# Probe-Scope_Controller_v1_0.net
KiCad netlist of a schematic drawn in Altium Designer
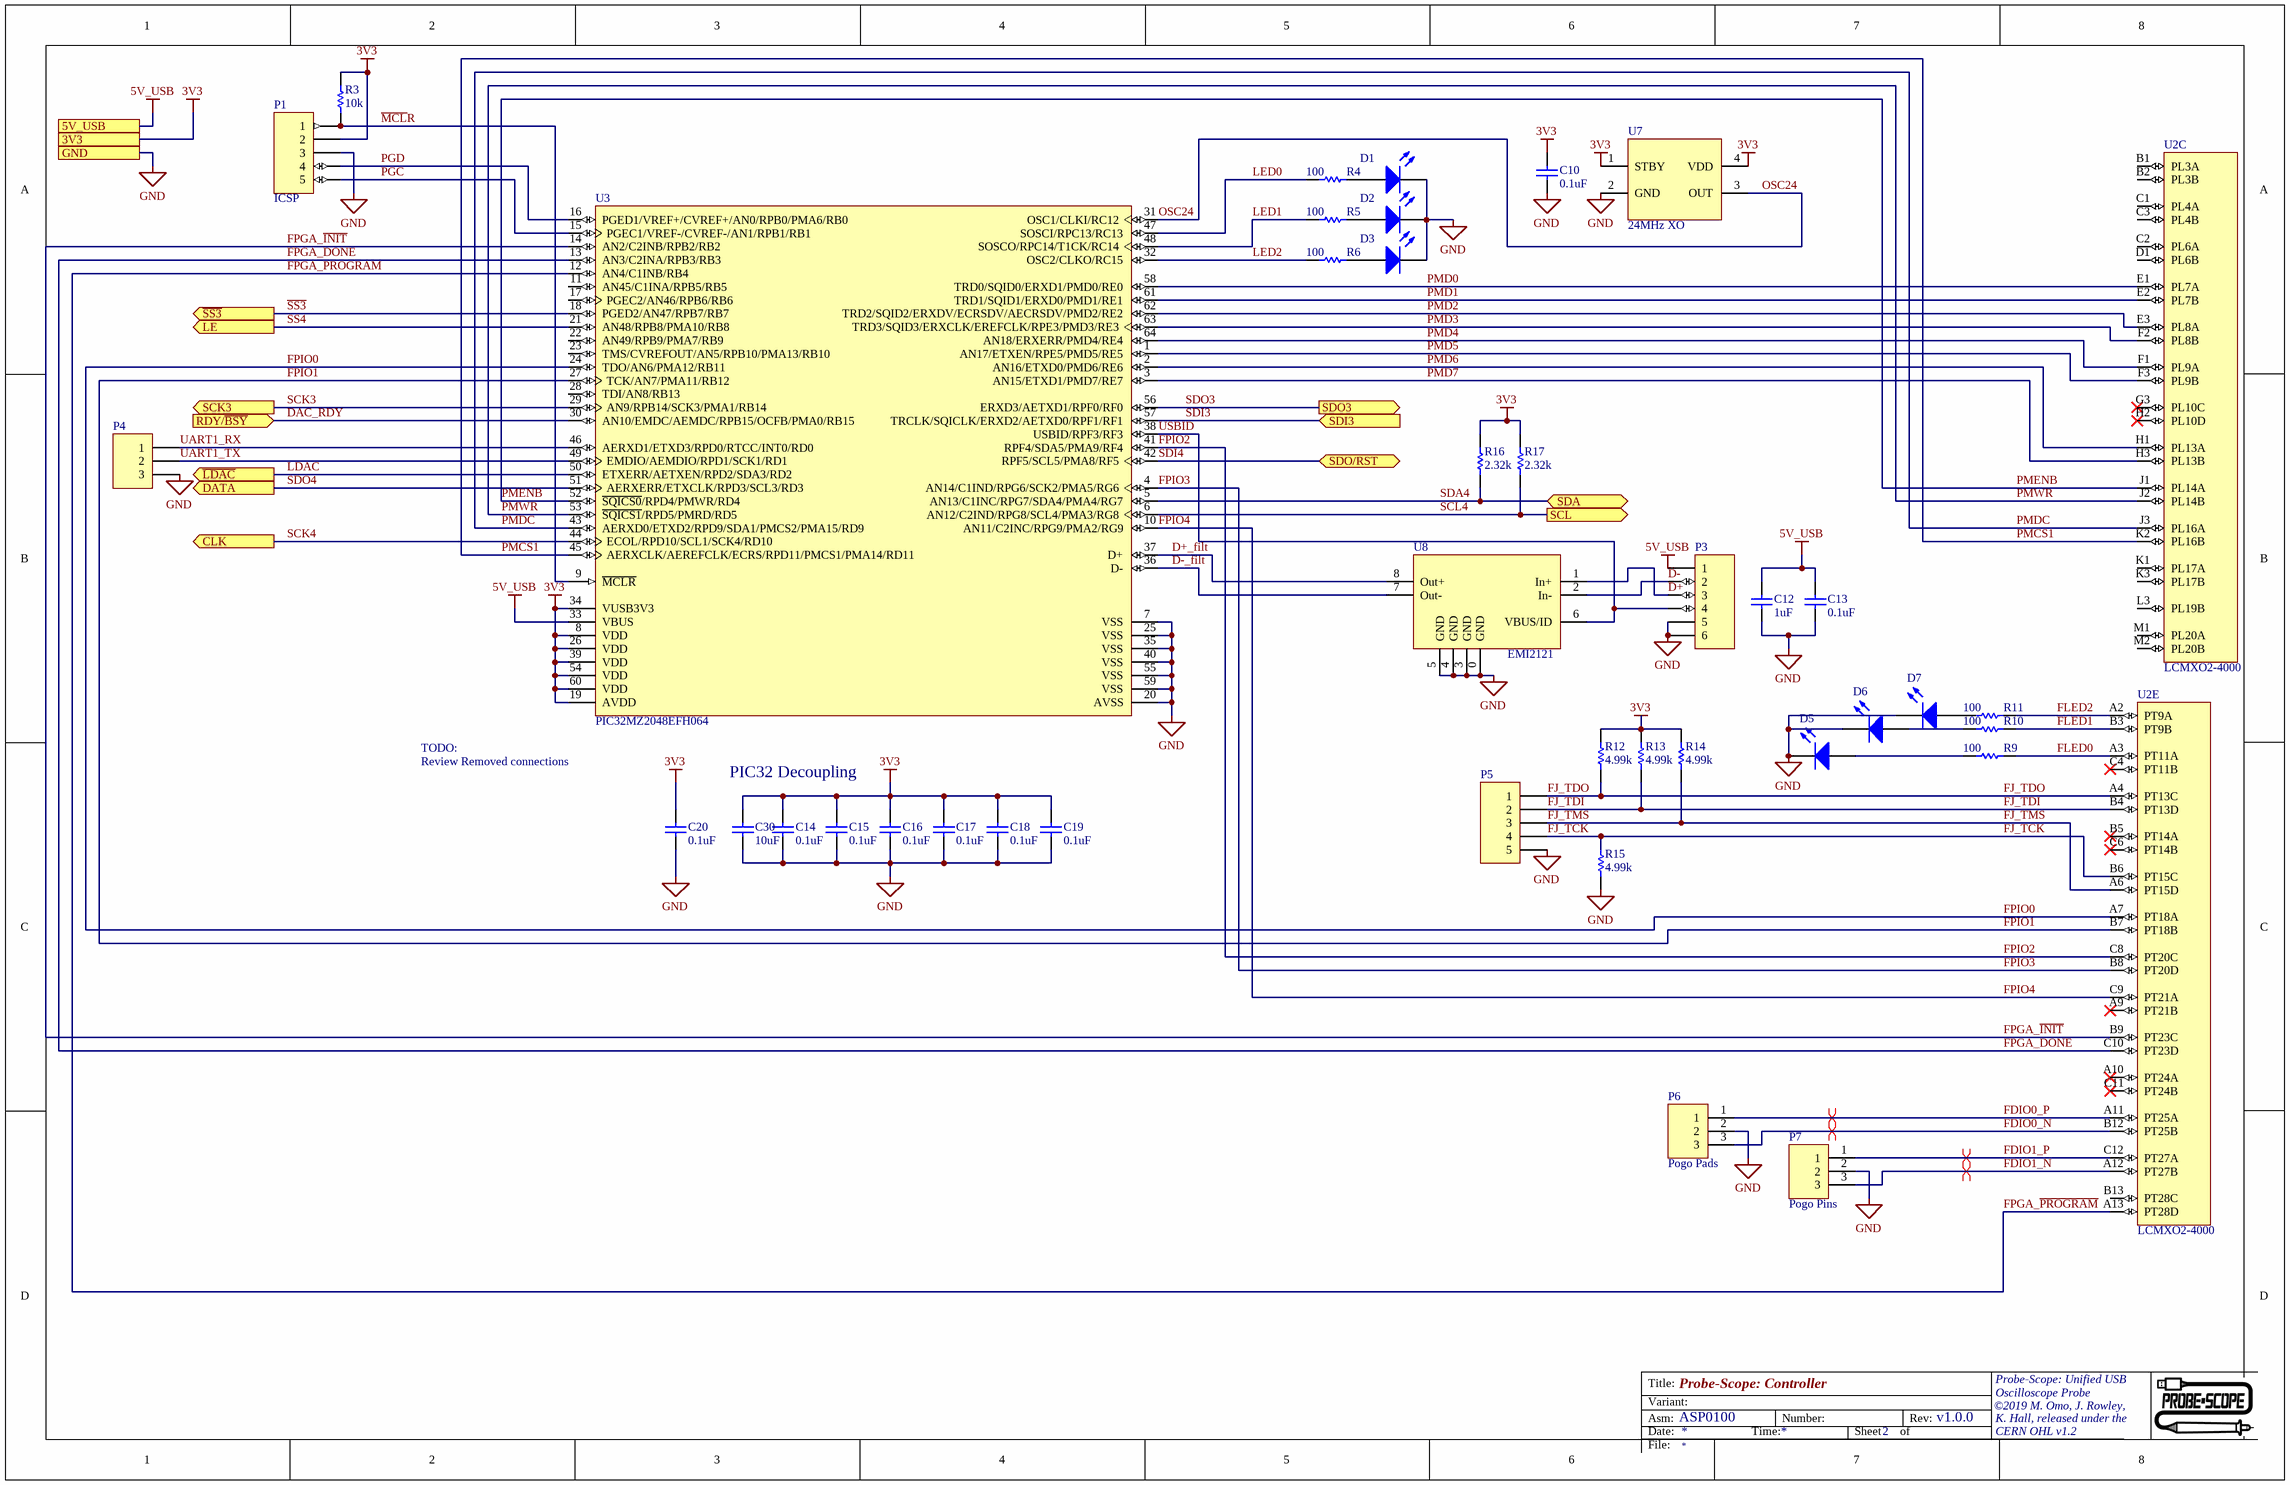
[diagram p0: Probe-Scope Controller v1.0.SchDoc]

(export (version "E")
  (design (tool "Eeschema 10.0.6"))
  (components
    (comp (ref "C10")
      (value "0.1uF")
      (footprint "0402(1005)")
      (fields
        (field (name "MANF") "Samsung Electro-Mechanics")
        (field (name "TOLERANCE") "10")
        (field (name "VOLTAGE") "6.3")
        (field (name "MODIFIED BY") "jrowley")
        (field (name "APPROVED") "False")
      )
      (libsource (lib "MENG Database Library VPN") (part "Cap"))
    )
    (comp (ref "C12")
      (value "1uF")
      (footprint "0402(1005)")
      (fields
        (field (name "MANF") "Murata Electronics")
        (field (name "TOLERANCE") "10")
        (field (name "Comment") "10V")
        (field (name "MODIFIED BY") "jrowley")
        (field (name "APPROVED") "False")
      )
      (libsource (lib "MENG Database Library VPN") (part "Cap"))
    )
    (comp (ref "C13")
      (value "0.1uF")
      (footprint "0402(1005)")
      (fields
        (field (name "MANF") "Samsung Electro-Mechanics")
        (field (name "TOLERANCE") "10")
        (field (name "VOLTAGE") "6.3")
        (field (name "MODIFIED BY") "jrowley")
        (field (name "APPROVED") "False")
      )
      (libsource (lib "MENG Database Library VPN") (part "Cap"))
    )
    (comp (ref "C14")
      (value "0.1uF")
      (footprint "0402(1005)")
      (fields
        (field (name "MANF") "Samsung Electro-Mechanics")
        (field (name "TOLERANCE") "10")
        (field (name "VOLTAGE") "6.3")
        (field (name "MODIFIED BY") "jrowley")
        (field (name "APPROVED") "False")
      )
      (libsource (lib "MENG Database Library VPN") (part "Cap"))
    )
    (comp (ref "C15")
      (value "0.1uF")
      (footprint "0402(1005)")
      (fields
        (field (name "MANF") "Samsung Electro-Mechanics")
        (field (name "TOLERANCE") "10")
        (field (name "VOLTAGE") "6.3")
        (field (name "MODIFIED BY") "jrowley")
        (field (name "APPROVED") "False")
      )
      (libsource (lib "MENG Database Library VPN") (part "Cap"))
    )
    (comp (ref "C16")
      (value "0.1uF")
      (footprint "0402(1005)")
      (fields
        (field (name "MANF") "Samsung Electro-Mechanics")
        (field (name "TOLERANCE") "10")
        (field (name "VOLTAGE") "6.3")
        (field (name "MODIFIED BY") "jrowley")
        (field (name "APPROVED") "False")
      )
      (libsource (lib "MENG Database Library VPN") (part "Cap"))
    )
    (comp (ref "C17")
      (value "0.1uF")
      (footprint "0402(1005)")
      (fields
        (field (name "MANF") "Samsung Electro-Mechanics")
        (field (name "TOLERANCE") "10")
        (field (name "VOLTAGE") "6.3")
        (field (name "MODIFIED BY") "jrowley")
        (field (name "APPROVED") "False")
      )
      (libsource (lib "MENG Database Library VPN") (part "Cap"))
    )
    (comp (ref "C18")
      (value "0.1uF")
      (footprint "0402(1005)")
      (fields
        (field (name "MANF") "Samsung Electro-Mechanics")
        (field (name "TOLERANCE") "10")
        (field (name "VOLTAGE") "6.3")
        (field (name "MODIFIED BY") "jrowley")
        (field (name "APPROVED") "False")
      )
      (libsource (lib "MENG Database Library VPN") (part "Cap"))
    )
    (comp (ref "C19")
      (value "0.1uF")
      (footprint "0402(1005)")
      (fields
        (field (name "MANF") "Samsung Electro-Mechanics")
        (field (name "TOLERANCE") "10")
        (field (name "VOLTAGE") "6.3")
        (field (name "MODIFIED BY") "jrowley")
        (field (name "APPROVED") "False")
      )
      (libsource (lib "MENG Database Library VPN") (part "Cap"))
    )
    (comp (ref "C20")
      (value "0.1uF")
      (footprint "0402(1005)")
      (fields
        (field (name "MANF") "Samsung Electro-Mechanics")
        (field (name "TOLERANCE") "10")
        (field (name "VOLTAGE") "6.3")
        (field (name "MODIFIED BY") "jrowley")
        (field (name "APPROVED") "False")
      )
      (libsource (lib "MENG Database Library VPN") (part "Cap"))
    )
    (comp (ref "C30")
      (value "10uF")
      (footprint "0603(1608)")
      (fields
        (field (name "MANF") "Samsung Electro-Mechanics")
        (field (name "TOLERANCE") "20")
        (field (name "VOLTAGE") "25")
        (field (name "MODIFIED BY") "sotterbacher")
        (field (name "APPROVED") "True")
      )
      (libsource (lib "MENG Database Library VPN") (part "Cap"))
    )
    (comp (ref "D1")
      (value "Green")
      (footprint "0603(1608) LED")
      (fields
        (field (name "MANF") "OSRAM")
        (field (name "VOLTAGE") "1.7")
        (field (name "MODIFIED BY") "pmarcus")
        (field (name "APPROVED") "True")
      )
      (libsource (lib "MENG Database Library VPN") (part "LED0"))
    )
    (comp (ref "D2")
      (value "Green")
      (footprint "0603(1608) LED")
      (fields
        (field (name "MANF") "OSRAM")
        (field (name "VOLTAGE") "1.7")
        (field (name "MODIFIED BY") "pmarcus")
        (field (name "APPROVED") "True")
      )
      (libsource (lib "MENG Database Library VPN") (part "LED0"))
    )
    (comp (ref "D3")
      (value "Green")
      (footprint "0603(1608) LED")
      (fields
        (field (name "MANF") "OSRAM")
        (field (name "VOLTAGE") "1.7")
        (field (name "MODIFIED BY") "pmarcus")
        (field (name "APPROVED") "True")
      )
      (libsource (lib "MENG Database Library VPN") (part "LED0"))
    )
    (comp (ref "D5")
      (value "Green")
      (footprint "0603(1608) LED")
      (fields
        (field (name "MANF") "OSRAM")
        (field (name "VOLTAGE") "1.7")
        (field (name "MODIFIED BY") "pmarcus")
        (field (name "APPROVED") "True")
      )
      (libsource (lib "MENG Database Library VPN") (part "LED0"))
    )
    (comp (ref "D6")
      (value "Green")
      (footprint "0603(1608) LED")
      (fields
        (field (name "MANF") "OSRAM")
        (field (name "VOLTAGE") "1.7")
        (field (name "MODIFIED BY") "pmarcus")
        (field (name "APPROVED") "True")
      )
      (libsource (lib "MENG Database Library VPN") (part "LED0"))
    )
    (comp (ref "D7")
      (value "Green")
      (footprint "0603(1608) LED")
      (fields
        (field (name "MANF") "OSRAM")
        (field (name "VOLTAGE") "1.7")
        (field (name "MODIFIED BY") "pmarcus")
        (field (name "APPROVED") "True")
      )
      (libsource (lib "MENG Database Library VPN") (part "LED0"))
    )
    (comp (ref "P1")
      (value "ICSP")
      (footprint "MOLEX PICOBLADE 5 POS")
      (fields
        (field (name "MANF") "Molex")
        (field (name "VOLTAGE") "125")
        (field (name "MODIFIED BY") "pmarcus")
        (field (name "APPROVED") "True")
      )
      (libsource (lib "MENG Database Library VPN") (part "Header 5"))
    )
    (comp (ref "P3")
      (value "Micro USB")
      (footprint "USB Micro B ZX62")
      (fields
        (field (name "MANF") "Amphenol FCI")
        (field (name "VOLTAGE") "100")
        (field (name "MODIFIED BY") "jrowley")
        (field (name "APPROVED") "False")
      )
      (libsource (lib "MENG Database Library VPN") (part "Header 6"))
    )
    (comp (ref "P4")
      (value "PicoBlade 3")
      (footprint "MOLEX PICOBLADE 3 POS")
      (fields
        (field (name "MANF") "Molex")
        (field (name "VOLTAGE") "125")
        (field (name "MODIFIED BY") "rlaity")
        (field (name "APPROVED") "True")
      )
      (libsource (lib "MENG Database Library 18") (part "Header 3"))
    )
    (comp (ref "P5")
      (value "PicoBlade 5")
      (footprint "MOLEX PICOBLADE 5 POS")
      (fields
        (field (name "MANF") "Molex")
        (field (name "VOLTAGE") "125")
        (field (name "MODIFIED BY") "pmarcus")
        (field (name "APPROVED") "True")
      )
      (libsource (lib "MENG Database Library 18") (part "Header 5"))
    )
    (comp (ref "P6")
      (value "Pogo Pads")
      (footprint "POGO_PADS_3")
      (libsource (lib "PS v1.0") (part "POGO_PADS_3"))
    )
    (comp (ref "P7")
      (value "Pogo Pins")
      (footprint "POGO_PINS_3")
      (fields (field (name "MANF") "Prec-Dip"))
      (libsource (lib "PS v1.0") (part "POGO_PINS_3"))
    )
    (comp (ref "R3")
      (value "10k")
      (footprint "0402(1005)")
      (fields
        (field (name "MANF") "Stackpole Electronics")
        (field (name "TOLERANCE") "1")
        (field (name "POWER") "0.0625")
        (field (name "MODIFIED BY") "jrowley")
        (field (name "APPROVED") "False")
      )
      (libsource (lib "MENG Database Library VPN") (part "Res1"))
    )
    (comp (ref "R4")
      (value "100")
      (footprint "0402(1005)")
      (fields
        (field (name "MANF") "Yageo")
        (field (name "TOLERANCE") "1")
        (field (name "POWER") "0.0625")
        (field (name "MODIFIED BY") "jrowley")
        (field (name "APPROVED") "False")
      )
      (libsource (lib "MENG Database Library VPN") (part "Res1"))
    )
    (comp (ref "R5")
      (value "100")
      (footprint "0402(1005)")
      (fields
        (field (name "MANF") "Yageo")
        (field (name "TOLERANCE") "1")
        (field (name "POWER") "0.0625")
        (field (name "MODIFIED BY") "jrowley")
        (field (name "APPROVED") "False")
      )
      (libsource (lib "MENG Database Library VPN") (part "Res1"))
    )
    (comp (ref "R6")
      (value "100")
      (footprint "0402(1005)")
      (fields
        (field (name "MANF") "Yageo")
        (field (name "TOLERANCE") "1")
        (field (name "POWER") "0.0625")
        (field (name "MODIFIED BY") "jrowley")
        (field (name "APPROVED") "False")
      )
      (libsource (lib "MENG Database Library VPN") (part "Res1"))
    )
    (comp (ref "R9")
      (value "100")
      (footprint "0402(1005)")
      (fields
        (field (name "MANF") "Yageo")
        (field (name "TOLERANCE") "1")
        (field (name "POWER") "0.0625")
        (field (name "MODIFIED BY") "jrowley")
        (field (name "APPROVED") "False")
      )
      (libsource (lib "MENG Database Library VPN") (part "Res1"))
    )
    (comp (ref "R10")
      (value "100")
      (footprint "0402(1005)")
      (fields
        (field (name "MANF") "Yageo")
        (field (name "TOLERANCE") "1")
        (field (name "POWER") "0.0625")
        (field (name "MODIFIED BY") "jrowley")
        (field (name "APPROVED") "False")
      )
      (libsource (lib "MENG Database Library VPN") (part "Res1"))
    )
    (comp (ref "R11")
      (value "100")
      (footprint "0402(1005)")
      (fields
        (field (name "MANF") "Yageo")
        (field (name "TOLERANCE") "1")
        (field (name "POWER") "0.0625")
        (field (name "MODIFIED BY") "jrowley")
        (field (name "APPROVED") "False")
      )
      (libsource (lib "MENG Database Library VPN") (part "Res1"))
    )
    (comp (ref "R12")
      (value "4.99k")
      (footprint "0402(1005)")
      (fields
        (field (name "MANF") "Yageo")
        (field (name "TOLERANCE") "1")
        (field (name "POWER") "0.063")
        (field (name "MODIFIED BY") "khall")
        (field (name "APPROVED") "False")
      )
      (libsource (lib "MENG Database Library VPN") (part "Res1"))
    )
    (comp (ref "R13")
      (value "4.99k")
      (footprint "0402(1005)")
      (fields
        (field (name "MANF") "Yageo")
        (field (name "TOLERANCE") "1")
        (field (name "POWER") "0.063")
        (field (name "MODIFIED BY") "khall")
        (field (name "APPROVED") "False")
      )
      (libsource (lib "MENG Database Library VPN") (part "Res1"))
    )
    (comp (ref "R14")
      (value "4.99k")
      (footprint "0402(1005)")
      (fields
        (field (name "MANF") "Yageo")
        (field (name "TOLERANCE") "1")
        (field (name "POWER") "0.063")
        (field (name "MODIFIED BY") "khall")
        (field (name "APPROVED") "False")
      )
      (libsource (lib "MENG Database Library VPN") (part "Res1"))
    )
    (comp (ref "R15")
      (value "4.99k")
      (footprint "0402(1005)")
      (fields
        (field (name "MANF") "Yageo")
        (field (name "TOLERANCE") "1")
        (field (name "POWER") "0.063")
        (field (name "MODIFIED BY") "khall")
        (field (name "APPROVED") "False")
      )
      (libsource (lib "MENG Database Library VPN") (part "Res1"))
    )
    (comp (ref "R16")
      (value "2.32k")
      (footprint "0402(1005)")
      (fields
        (field (name "MANF") "Stackpole Electronics")
        (field (name "TOLERANCE") "1")
        (field (name "POWER") "0.0625")
        (field (name "MODIFIED BY") "khall")
        (field (name "APPROVED") "False")
      )
      (libsource (lib "MENG Database Library VPN") (part "Res1"))
    )
    (comp (ref "R17")
      (value "2.32k")
      (footprint "0402(1005)")
      (fields
        (field (name "MANF") "Stackpole Electronics")
        (field (name "TOLERANCE") "1")
        (field (name "POWER") "0.0625")
        (field (name "MODIFIED BY") "khall")
        (field (name "APPROVED") "False")
      )
      (libsource (lib "MENG Database Library VPN") (part "Res1"))
    )
    (comp (ref "U2")
      (value "LCMXO2-4000")
      (footprint "132_Ball_csBGA_MachXO2")
      (fields (field (name "MANF") "Lattice Semiconductor"))
      (libsource (lib "PS v1.0") (part "MachXO2-4000"))
    )
    (comp (ref "U3")
      (value "PIC32MZ2048EFH064")
      (footprint "TSQFP50P1200X1200X120-64L")
      (description "Microchip PIC32MZ EF Series 64-pin")
      (fields (field (name "MANF") "Microchip Technology"))
      (libsource (lib "PS v1.0") (part "PIC32MZ2048EFH064-I/PT"))
    )
    (comp (ref "U7")
      (value "24MHz XO")
      (footprint "DSC60xxC")
      (fields
        (field (name "MANF") "Microchip")
        (field (name "MODIFIED BY") "jrowley")
        (field (name "APPROVED") "False")
      )
      (libsource (lib "MENG Database Library VPN") (part "DSC60x1"))
    )
    (comp (ref "U8")
      (value "EMI2121")
      (footprint "EMI2121")
      (fields
        (field (name "MANF") "On Semiconductor")
        (field (name "MODIFIED BY") "jrowley")
        (field (name "APPROVED") "False")
      )
      (libsource (lib "MENG Database Library VPN") (part "EMI2121"))
    )
  )
  (nets
    (net (code "1") (name "/D+") (class "Default")
      (node (ref "P3") (pin "3") (pinfunction "3_3") (pintype "bidirectional"))
      (node (ref "U8") (pin "1") (pinfunction "In+_1") (pintype "passive"))
    )
    (net (code "2") (name "/D+_filt") (class "Default")
      (node (ref "U3") (pin "37") (pinfunction "D+_37") (pintype "bidirectional"))
      (node (ref "U8") (pin "8") (pinfunction "Out+_8") (pintype "passive"))
    )
    (net (code "3") (name "/D-") (class "Default")
      (node (ref "P3") (pin "2") (pinfunction "2_2") (pintype "bidirectional"))
      (node (ref "U8") (pin "2") (pinfunction "In-_2") (pintype "passive"))
    )
    (net (code "4") (name "/D-_filt") (class "Default")
      (node (ref "U3") (pin "36") (pinfunction "D-_36") (pintype "bidirectional"))
      (node (ref "U8") (pin "7") (pinfunction "Out-_7") (pintype "passive"))
    )
    (net (code "5") (name "/DAC_RDY") (class "Default")
      (node (ref "U3") (pin "30") (pinfunction "AN10/EMDC/AEMDC/RPB15/OCFB/PMA0/RB15_30") (pintype "bidirectional"))
    )
    (net (code "6") (name "/FDIO0_N") (class "Default")
      (node (ref "P6") (pin "3") (pinfunction "3_3") (pintype "passive"))
      (node (ref "U2") (pin "B12") (pinfunction "PT25B_B12") (pintype "bidirectional"))
    )
    (net (code "7") (name "/FDIO0_P") (class "Default")
      (node (ref "P6") (pin "1") (pinfunction "1_1") (pintype "passive"))
      (node (ref "U2") (pin "A11") (pinfunction "PT25A_A11") (pintype "bidirectional"))
    )
    (net (code "8") (name "/FDIO1_N") (class "Default")
      (node (ref "P7") (pin "3") (pinfunction "3_3") (pintype "passive"))
      (node (ref "U2") (pin "A12") (pinfunction "PT27B_A12") (pintype "bidirectional"))
    )
    (net (code "9") (name "/FDIO1_P") (class "Default")
      (node (ref "P7") (pin "1") (pinfunction "1_1") (pintype "passive"))
      (node (ref "U2") (pin "C12") (pinfunction "PT27A_C12") (pintype "bidirectional"))
    )
    (net (code "10") (name "/FJ_TCK") (class "Default")
      (node (ref "P5") (pin "4") (pinfunction "4_4") (pintype "passive"))
      (node (ref "R15") (pin "2") (pinfunction "2_2") (pintype "passive"))
      (node (ref "U2") (pin "B6") (pinfunction "PT15C_B6") (pintype "bidirectional"))
    )
    (net (code "11") (name "/FJ_TDI") (class "Default")
      (node (ref "P5") (pin "2") (pinfunction "2_2") (pintype "passive"))
      (node (ref "R13") (pin "1") (pinfunction "1_1") (pintype "passive"))
      (node (ref "U2") (pin "B4") (pinfunction "PT13D_B4") (pintype "bidirectional"))
    )
    (net (code "12") (name "/FJ_TDO") (class "Default")
      (node (ref "P5") (pin "1") (pinfunction "1_1") (pintype "passive"))
      (node (ref "R12") (pin "1") (pinfunction "1_1") (pintype "passive"))
      (node (ref "U2") (pin "A4") (pinfunction "PT13C_A4") (pintype "bidirectional"))
    )
    (net (code "13") (name "/FJ_TMS") (class "Default")
      (node (ref "P5") (pin "3") (pinfunction "3_3") (pintype "passive"))
      (node (ref "R14") (pin "1") (pinfunction "1_1") (pintype "passive"))
      (node (ref "U2") (pin "A6") (pinfunction "PT15D_A6") (pintype "bidirectional"))
    )
    (net (code "14") (name "/FLED0") (class "Default")
      (node (ref "R9") (pin "2") (pinfunction "2_2") (pintype "passive"))
      (node (ref "U2") (pin "A3") (pinfunction "PT11A_A3") (pintype "bidirectional"))
    )
    (net (code "15") (name "/FLED1") (class "Default")
      (node (ref "R10") (pin "2") (pinfunction "2_2") (pintype "passive"))
      (node (ref "U2") (pin "B3") (pinfunction "PT9B_B3") (pintype "bidirectional"))
    )
    (net (code "16") (name "/FLED2") (class "Default")
      (node (ref "R11") (pin "2") (pinfunction "2_2") (pintype "passive"))
      (node (ref "U2") (pin "A2") (pinfunction "PT9A_A2") (pintype "bidirectional"))
    )
    (net (code "17") (name "/FPGA_DONE") (class "Default")
      (node (ref "U2") (pin "C10") (pinfunction "PT23D_C10") (pintype "bidirectional"))
      (node (ref "U3") (pin "13") (pinfunction "AN3/C2INA/RPB3/RB3_13") (pintype "bidirectional"))
    )
    (net (code "18") (name "/FPGA_~{INIT}") (class "Default")
      (node (ref "U2") (pin "B9") (pinfunction "PT23C_B9") (pintype "bidirectional"))
      (node (ref "U3") (pin "14") (pinfunction "AN2/C2INB/RPB2/RB2_14") (pintype "bidirectional"))
    )
    (net (code "19") (name "/FPGA_~{PROGRAM}") (class "Default")
      (node (ref "U2") (pin "A13") (pinfunction "PT28D_A13") (pintype "bidirectional"))
      (node (ref "U3") (pin "12") (pinfunction "AN4/C1INB/RB4_12") (pintype "bidirectional"))
    )
    (net (code "20") (name "/FPIO0") (class "Default")
      (node (ref "U2") (pin "A7") (pinfunction "PT18A_A7") (pintype "bidirectional"))
      (node (ref "U3") (pin "24") (pinfunction "TDO/AN6/PMA12/RB11_24") (pintype "bidirectional"))
    )
    (net (code "21") (name "/FPIO1") (class "Default")
      (node (ref "U2") (pin "B7") (pinfunction "PT18B_B7") (pintype "bidirectional"))
      (node (ref "U3") (pin "27") (pinfunction "TCK/AN7/PMA11/RB12_27") (pintype "bidirectional"))
    )
    (net (code "22") (name "/FPIO2") (class "Default")
      (node (ref "U2") (pin "C8") (pinfunction "PT20C_C8") (pintype "bidirectional"))
      (node (ref "U3") (pin "41") (pinfunction "RPF4/SDA5/PMA9/RF4_41") (pintype "bidirectional"))
    )
    (net (code "23") (name "/FPIO3") (class "Default")
      (node (ref "U2") (pin "B8") (pinfunction "PT20D_B8") (pintype "bidirectional"))
      (node (ref "U3") (pin "4") (pinfunction "AN14/C1IND/RPG6/SCK2/PMA5/RG6_4") (pintype "bidirectional"))
    )
    (net (code "24") (name "/FPIO4") (class "Default")
      (node (ref "U2") (pin "C9") (pinfunction "PT21A_C9") (pintype "bidirectional"))
      (node (ref "U3") (pin "10") (pinfunction "AN11/C2INC/RPG9/PMA2/RG9_10") (pintype "bidirectional"))
    )
    (net (code "25") (name "/LED0") (class "Default")
      (node (ref "R4") (pin "1") (pinfunction "1_1") (pintype "passive"))
      (node (ref "U3") (pin "47") (pinfunction "SOSCI/RPC13/RC13_47") (pintype "bidirectional"))
    )
    (net (code "26") (name "/LED1") (class "Default")
      (node (ref "R5") (pin "1") (pinfunction "1_1") (pintype "passive"))
      (node (ref "U3") (pin "48") (pinfunction "SOSCO/RPC14/T1CK/RC14_48") (pintype "bidirectional"))
    )
    (net (code "27") (name "/LED2") (class "Default")
      (node (ref "R6") (pin "1") (pinfunction "1_1") (pintype "passive"))
      (node (ref "U3") (pin "32") (pinfunction "OSC2/CLKO/RC15_32") (pintype "bidirectional"))
    )
    (net (code "28") (name "/OSC24") (class "Default")
      (node (ref "U3") (pin "31") (pinfunction "OSC1/CLKI/RC12_31") (pintype "bidirectional"))
      (node (ref "U7") (pin "3") (pinfunction "OUT_3") (pintype "passive"))
    )
    (net (code "29") (name "/PGC") (class "Default")
      (node (ref "P1") (pin "5") (pinfunction "5_5") (pintype "bidirectional"))
      (node (ref "U3") (pin "15") (pinfunction "PGEC1/VREF-/CVREF-/AN1/RPB1/RB1_15") (pintype "bidirectional"))
    )
    (net (code "30") (name "/PGD") (class "Default")
      (node (ref "P1") (pin "4") (pinfunction "4_4") (pintype "bidirectional"))
      (node (ref "U3") (pin "16") (pinfunction "PGED1/VREF+/CVREF+/AN0/RPB0/PMA6/RB0_16") (pintype "bidirectional"))
    )
    (net (code "31") (name "/PMCS1") (class "Default")
      (node (ref "U2") (pin "K2") (pinfunction "PL16B_K2") (pintype "bidirectional"))
      (node (ref "U3") (pin "45") (pinfunction "AERXCLK/AEREFCLK/ECRS/RPD11/PMCS1/PMA14/RD11_45") (pintype "bidirectional"))
    )
    (net (code "32") (name "/PMD0") (class "Default")
      (node (ref "U2") (pin "E1") (pinfunction "PL7A_E1") (pintype "bidirectional"))
      (node (ref "U3") (pin "58") (pinfunction "TRD0/SQID0/ERXD1/PMD0/RE0_58") (pintype "bidirectional"))
    )
    (net (code "33") (name "/PMD1") (class "Default")
      (node (ref "U2") (pin "E2") (pinfunction "PL7B_E2") (pintype "bidirectional"))
      (node (ref "U3") (pin "61") (pinfunction "TRD1/SQID1/ERXD0/PMD1/RE1_61") (pintype "bidirectional"))
    )
    (net (code "34") (name "/PMD2") (class "Default")
      (node (ref "U2") (pin "E3") (pinfunction "PL8A_E3") (pintype "bidirectional"))
      (node (ref "U3") (pin "62") (pinfunction "TRD2/SQID2/ERXDV/ECRSDV/AECRSDV/PMD2/RE2_62") (pintype "bidirectional"))
    )
    (net (code "35") (name "/PMD3") (class "Default")
      (node (ref "U2") (pin "F2") (pinfunction "PL8B_F2") (pintype "bidirectional"))
      (node (ref "U3") (pin "63") (pinfunction "TRD3/SQID3/ERXCLK/EREFCLK/RPE3/PMD3/RE3_63") (pintype "bidirectional"))
    )
    (net (code "36") (name "/PMD4") (class "Default")
      (node (ref "U2") (pin "F1") (pinfunction "PL9A_F1") (pintype "bidirectional"))
      (node (ref "U3") (pin "64") (pinfunction "AN18/ERXERR/PMD4/RE4_64") (pintype "bidirectional"))
    )
    (net (code "37") (name "/PMD5") (class "Default")
      (node (ref "U2") (pin "F3") (pinfunction "PL9B_F3") (pintype "bidirectional"))
      (node (ref "U3") (pin "1") (pinfunction "AN17/ETXEN/RPE5/PMD5/RE5_1") (pintype "bidirectional"))
    )
    (net (code "38") (name "/PMD6") (class "Default")
      (node (ref "U2") (pin "H1") (pinfunction "PL13A_H1") (pintype "bidirectional"))
      (node (ref "U3") (pin "2") (pinfunction "AN16/ETXD0/PMD6/RE6_2") (pintype "bidirectional"))
    )
    (net (code "39") (name "/PMD7") (class "Default")
      (node (ref "U2") (pin "H3") (pinfunction "PL13B_H3") (pintype "bidirectional"))
      (node (ref "U3") (pin "3") (pinfunction "AN15/ETXD1/PMD7/RE7_3") (pintype "bidirectional"))
    )
    (net (code "40") (name "/PMDC") (class "Default")
      (node (ref "U2") (pin "J3") (pinfunction "PL16A_J3") (pintype "bidirectional"))
      (node (ref "U3") (pin "43") (pinfunction "AERXD0/ETXD2/RPD9/SDA1/PMCS2/PMA15/RD9_43") (pintype "bidirectional"))
    )
    (net (code "41") (name "/PMENB") (class "Default")
      (node (ref "U2") (pin "J1") (pinfunction "PL14A_J1") (pintype "bidirectional"))
      (node (ref "U3") (pin "52") (pinfunction "~{SQICS0}/RPD4/PMWR/RD4_52") (pintype "bidirectional"))
    )
    (net (code "42") (name "/SCK3") (class "Default")
      (node (ref "U3") (pin "29") (pinfunction "AN9/RPB14/SCK3/PMA1/RB14_29") (pintype "bidirectional"))
    )
    (net (code "43") (name "/SCK4") (class "Default")
      (node (ref "U3") (pin "44") (pinfunction "ECOL/RPD10/SCL1/SCK4/RD10_44") (pintype "bidirectional"))
    )
    (net (code "44") (name "/SCL4") (class "Default")
      (node (ref "R17") (pin "1") (pinfunction "1_1") (pintype "passive"))
      (node (ref "U3") (pin "6") (pinfunction "AN12/C2IND/RPG8/SCL4/PMA3/RG8_6") (pintype "bidirectional"))
    )
    (net (code "45") (name "/SDA4") (class "Default")
      (node (ref "R16") (pin "1") (pinfunction "1_1") (pintype "passive"))
      (node (ref "U3") (pin "5") (pinfunction "AN13/C1INC/RPG7/SDA4/PMA4/RG7_5") (pintype "bidirectional"))
    )
    (net (code "46") (name "/SDI3") (class "Default")
      (node (ref "U3") (pin "57") (pinfunction "TRCLK/SQICLK/ERXD2/AETXD0/RPF1/RF1_57") (pintype "bidirectional"))
    )
    (net (code "47") (name "/SDI4") (class "Default")
      (node (ref "U3") (pin "42") (pinfunction "RPF5/SCL5/PMA8/RF5_42") (pintype "bidirectional"))
    )
    (net (code "48") (name "/SDO3") (class "Default")
      (node (ref "U3") (pin "56") (pinfunction "ERXD3/AETXD1/RPF0/RF0_56") (pintype "bidirectional"))
    )
    (net (code "49") (name "/SDO4") (class "Default")
      (node (ref "U3") (pin "51") (pinfunction "AERXERR/ETXCLK/RPD3/SCL3/RD3_51") (pintype "bidirectional"))
    )
    (net (code "50") (name "/UART1_RX") (class "Default")
      (node (ref "P4") (pin "1") (pinfunction "1_1") (pintype "passive"))
      (node (ref "U3") (pin "46") (pinfunction "AERXD1/ETXD3/RPD0/RTCC/INT0/RD0_46") (pintype "bidirectional"))
    )
    (net (code "51") (name "/UART1_TX") (class "Default")
      (node (ref "P4") (pin "2") (pinfunction "2_2") (pintype "passive"))
      (node (ref "U3") (pin "49") (pinfunction "EMDIO/AEMDIO/RPD1/SCK1/RD1_49") (pintype "bidirectional"))
    )
    (net (code "52") (name "/USBID") (class "Default")
      (node (ref "P3") (pin "4") (pinfunction "4_4") (pintype "bidirectional"))
      (node (ref "U3") (pin "38") (pinfunction "USBID/RPF3/RF3_38") (pintype "bidirectional"))
      (node (ref "U8") (pin "6") (pinfunction "VBUS/ID_6") (pintype "passive"))
    )
    (net (code "53") (name "/~{LDAC}") (class "Default")
      (node (ref "U3") (pin "50") (pinfunction "ETXERR/AETXEN/RPD2/SDA3/RD2_50") (pintype "bidirectional"))
    )
    (net (code "54") (name "/~{MCL}R") (class "Default")
      (node (ref "P1") (pin "1") (pinfunction "1_1") (pintype "output"))
      (node (ref "R3") (pin "1") (pinfunction "1_1") (pintype "passive"))
      (node (ref "U3") (pin "9") (pinfunction "~{MCLR}_9") (pintype "input"))
    )
    (net (code "55") (name "/~{PMW}R") (class "Default")
      (node (ref "U2") (pin "J2") (pinfunction "PL14B_J2") (pintype "bidirectional"))
      (node (ref "U3") (pin "53") (pinfunction "~{SQICS1}/RPD5/PMRD/RD5_53") (pintype "bidirectional"))
    )
    (net (code "56") (name "/~{SS3}") (class "Default")
      (node (ref "U3") (pin "18") (pinfunction "PGED2/AN47/RPB7/RB7_18") (pintype "bidirectional"))
    )
    (net (code "57") (name "/~{SS4}") (class "Default")
      (node (ref "U3") (pin "21") (pinfunction "AN48/RPB8/PMA10/RB8_21") (pintype "bidirectional"))
    )
    (net (code "58") (name "3V3") (class "Default")
      (node (ref "C10") (pin "2") (pinfunction "2_2") (pintype "passive"))
      (node (ref "C14") (pin "2") (pinfunction "2_2") (pintype "passive"))
      (node (ref "C15") (pin "2") (pinfunction "2_2") (pintype "passive"))
      (node (ref "C16") (pin "2") (pinfunction "2_2") (pintype "passive"))
      (node (ref "C17") (pin "2") (pinfunction "2_2") (pintype "passive"))
      (node (ref "C18") (pin "2") (pinfunction "2_2") (pintype "passive"))
      (node (ref "C19") (pin "2") (pinfunction "2_2") (pintype "passive"))
      (node (ref "C20") (pin "2") (pinfunction "2_2") (pintype "passive"))
      (node (ref "C30") (pin "2") (pinfunction "2_2") (pintype "passive"))
      (node (ref "P1") (pin "2") (pinfunction "2_2") (pintype "power_in"))
      (node (ref "R12") (pin "2") (pinfunction "2_2") (pintype "passive"))
      (node (ref "R13") (pin "2") (pinfunction "2_2") (pintype "passive"))
      (node (ref "R14") (pin "2") (pinfunction "2_2") (pintype "passive"))
      (node (ref "R16") (pin "2") (pinfunction "2_2") (pintype "passive"))
      (node (ref "R17") (pin "2") (pinfunction "2_2") (pintype "passive"))
      (node (ref "R3") (pin "2") (pinfunction "2_2") (pintype "passive"))
      (node (ref "U3") (pin "19") (pinfunction "AVDD_19") (pintype "power_in"))
      (node (ref "U3") (pin "26") (pinfunction "VDD_26") (pintype "power_in"))
      (node (ref "U3") (pin "34") (pinfunction "VUSB3V3_34") (pintype "power_in"))
      (node (ref "U3") (pin "39") (pinfunction "VDD_39") (pintype "power_in"))
      (node (ref "U3") (pin "54") (pinfunction "VDD_54") (pintype "power_in"))
      (node (ref "U3") (pin "60") (pinfunction "VDD_60") (pintype "power_in"))
      (node (ref "U3") (pin "8") (pinfunction "VDD_8") (pintype "power_in"))
      (node (ref "U7") (pin "1") (pinfunction "STBY_1") (pintype "passive"))
      (node (ref "U7") (pin "4") (pinfunction "VDD_4") (pintype "passive"))
    )
    (net (code "59") (name "5V_USB") (class "Default")
      (node (ref "C12") (pin "2") (pinfunction "2_2") (pintype "passive"))
      (node (ref "C13") (pin "2") (pinfunction "2_2") (pintype "passive"))
      (node (ref "P3") (pin "1") (pinfunction "1_1") (pintype "power_in"))
      (node (ref "U3") (pin "33") (pinfunction "VBUS_33") (pintype "power_in"))
    )
    (net (code "60") (name "GND") (class "Default")
      (node (ref "C10") (pin "1") (pinfunction "1_1") (pintype "passive"))
      (node (ref "C12") (pin "1") (pinfunction "1_1") (pintype "passive"))
      (node (ref "C13") (pin "1") (pinfunction "1_1") (pintype "passive"))
      (node (ref "C14") (pin "1") (pinfunction "1_1") (pintype "passive"))
      (node (ref "C15") (pin "1") (pinfunction "1_1") (pintype "passive"))
      (node (ref "C16") (pin "1") (pinfunction "1_1") (pintype "passive"))
      (node (ref "C17") (pin "1") (pinfunction "1_1") (pintype "passive"))
      (node (ref "C18") (pin "1") (pinfunction "1_1") (pintype "passive"))
      (node (ref "C19") (pin "1") (pinfunction "1_1") (pintype "passive"))
      (node (ref "C20") (pin "1") (pinfunction "1_1") (pintype "passive"))
      (node (ref "C30") (pin "1") (pinfunction "1_1") (pintype "passive"))
      (node (ref "D1") (pin "2") (pinfunction "K_2") (pintype "passive"))
      (node (ref "D2") (pin "2") (pinfunction "K_2") (pintype "passive"))
      (node (ref "D3") (pin "2") (pinfunction "K_2") (pintype "passive"))
      (node (ref "D5") (pin "2") (pinfunction "K_2") (pintype "passive"))
      (node (ref "D6") (pin "2") (pinfunction "K_2") (pintype "passive"))
      (node (ref "D7") (pin "2") (pinfunction "K_2") (pintype "passive"))
      (node (ref "P1") (pin "3") (pinfunction "3_3") (pintype "power_in"))
      (node (ref "P3") (pin "5") (pinfunction "5_5") (pintype "power_in"))
      (node (ref "P3") (pin "6") (pinfunction "6_6") (pintype "passive"))
      (node (ref "P4") (pin "3") (pinfunction "3_3") (pintype "passive"))
      (node (ref "P5") (pin "5") (pinfunction "5_5") (pintype "passive"))
      (node (ref "P6") (pin "2") (pinfunction "2_2") (pintype "passive"))
      (node (ref "P7") (pin "2") (pinfunction "2_2") (pintype "passive"))
      (node (ref "R15") (pin "1") (pinfunction "1_1") (pintype "passive"))
      (node (ref "U3") (pin "20") (pinfunction "AVSS_20") (pintype "power_in"))
      (node (ref "U3") (pin "25") (pinfunction "VSS_25") (pintype "power_in"))
      (node (ref "U3") (pin "35") (pinfunction "VSS_35") (pintype "power_in"))
      (node (ref "U3") (pin "40") (pinfunction "VSS_40") (pintype "power_in"))
      (node (ref "U3") (pin "55") (pinfunction "VSS_55") (pintype "power_in"))
      (node (ref "U3") (pin "59") (pinfunction "VSS_59") (pintype "power_in"))
      (node (ref "U3") (pin "7") (pinfunction "VSS_7") (pintype "power_in"))
      (node (ref "U7") (pin "2") (pinfunction "GND_2") (pintype "passive"))
      (node (ref "U8") (pin "0") (pinfunction "GND_0") (pintype "passive"))
      (node (ref "U8") (pin "3") (pinfunction "GND_3") (pintype "passive"))
      (node (ref "U8") (pin "4") (pinfunction "GND_4") (pintype "passive"))
      (node (ref "U8") (pin "5") (pinfunction "GND_5") (pintype "passive"))
    )
    (net (code "61") (name "Net-(D1-A)") (class "Default")
      (node (ref "D1") (pin "1") (pinfunction "A_1") (pintype "passive"))
      (node (ref "R4") (pin "2") (pinfunction "2_2") (pintype "passive"))
    )
    (net (code "62") (name "Net-(D2-A)") (class "Default")
      (node (ref "D2") (pin "1") (pinfunction "A_1") (pintype "passive"))
      (node (ref "R5") (pin "2") (pinfunction "2_2") (pintype "passive"))
    )
    (net (code "63") (name "Net-(D3-A)") (class "Default")
      (node (ref "D3") (pin "1") (pinfunction "A_1") (pintype "passive"))
      (node (ref "R6") (pin "2") (pinfunction "2_2") (pintype "passive"))
    )
    (net (code "64") (name "Net-(D5-A)") (class "Default")
      (node (ref "D5") (pin "1") (pinfunction "A_1") (pintype "passive"))
      (node (ref "R9") (pin "1") (pinfunction "1_1") (pintype "passive"))
    )
    (net (code "65") (name "Net-(D6-A)") (class "Default")
      (node (ref "D6") (pin "1") (pinfunction "A_1") (pintype "passive"))
      (node (ref "R10") (pin "1") (pinfunction "1_1") (pintype "passive"))
    )
    (net (code "66") (name "Net-(D7-A)") (class "Default")
      (node (ref "D7") (pin "1") (pinfunction "A_1") (pintype "passive"))
      (node (ref "R11") (pin "1") (pinfunction "1_1") (pintype "passive"))
    )
    (net (code "67") (name "unconnected-(U2C-PL3A-PadB1)") (class "Default")
      (node (ref "U2") (pin "B1") (pinfunction "PL3A_B1") (pintype "bidirectional"))
    )
    (net (code "68") (name "unconnected-(U2C-PL3B-PadB2)") (class "Default")
      (node (ref "U2") (pin "B2") (pinfunction "PL3B_B2") (pintype "bidirectional"))
    )
    (net (code "69") (name "unconnected-(U2C-PL4A-PadC1)") (class "Default")
      (node (ref "U2") (pin "C1") (pinfunction "PL4A_C1") (pintype "bidirectional"))
    )
    (net (code "70") (name "unconnected-(U2C-PL4B-PadC3)") (class "Default")
      (node (ref "U2") (pin "C3") (pinfunction "PL4B_C3") (pintype "bidirectional"))
    )
    (net (code "71") (name "unconnected-(U2C-PL6A-PadC2)") (class "Default")
      (node (ref "U2") (pin "C2") (pinfunction "PL6A_C2") (pintype "bidirectional"))
    )
    (net (code "72") (name "unconnected-(U2C-PL6B-PadD1)") (class "Default")
      (node (ref "U2") (pin "D1") (pinfunction "PL6B_D1") (pintype "bidirectional"))
    )
    (net (code "73") (name "unconnected-(U2C-PL10C-PadG3)") (class "Default")
      (node (ref "U2") (pin "G3") (pinfunction "PL10C_G3") (pintype "bidirectional+no_connect"))
    )
    (net (code "74") (name "unconnected-(U2C-PL10D-PadH2)") (class "Default")
      (node (ref "U2") (pin "H2") (pinfunction "PL10D_H2") (pintype "bidirectional+no_connect"))
    )
    (net (code "75") (name "unconnected-(U2C-PL17A-PadK1)") (class "Default")
      (node (ref "U2") (pin "K1") (pinfunction "PL17A_K1") (pintype "bidirectional"))
    )
    (net (code "76") (name "unconnected-(U2C-PL17B-PadK3)") (class "Default")
      (node (ref "U2") (pin "K3") (pinfunction "PL17B_K3") (pintype "bidirectional"))
    )
    (net (code "77") (name "unconnected-(U2C-PL19B-PadL3)") (class "Default")
      (node (ref "U2") (pin "L3") (pinfunction "PL19B_L3") (pintype "bidirectional"))
    )
    (net (code "78") (name "unconnected-(U2C-PL20A-PadM1)") (class "Default")
      (node (ref "U2") (pin "M1") (pinfunction "PL20A_M1") (pintype "bidirectional"))
    )
    (net (code "79") (name "unconnected-(U2C-PL20B-PadM2)") (class "Default")
      (node (ref "U2") (pin "M2") (pinfunction "PL20B_M2") (pintype "bidirectional"))
    )
    (net (code "80") (name "unconnected-(U2E-PT11B-PadC4)") (class "Default")
      (node (ref "U2") (pin "C4") (pinfunction "PT11B_C4") (pintype "bidirectional+no_connect"))
    )
    (net (code "81") (name "unconnected-(U2E-PT14A-PadB5)") (class "Default")
      (node (ref "U2") (pin "B5") (pinfunction "PT14A_B5") (pintype "bidirectional+no_connect"))
    )
    (net (code "82") (name "unconnected-(U2E-PT14B-PadC6)") (class "Default")
      (node (ref "U2") (pin "C6") (pinfunction "PT14B_C6") (pintype "bidirectional+no_connect"))
    )
    (net (code "83") (name "unconnected-(U2E-PT21B-PadA9)") (class "Default")
      (node (ref "U2") (pin "A9") (pinfunction "PT21B_A9") (pintype "bidirectional+no_connect"))
    )
    (net (code "84") (name "unconnected-(U2E-PT24A-PadA10)") (class "Default")
      (node (ref "U2") (pin "A10") (pinfunction "PT24A_A10") (pintype "bidirectional+no_connect"))
    )
    (net (code "85") (name "unconnected-(U2E-PT24B-PadC11)") (class "Default")
      (node (ref "U2") (pin "C11") (pinfunction "PT24B_C11") (pintype "bidirectional+no_connect"))
    )
    (net (code "86") (name "unconnected-(U2E-PT28C-PadB13)") (class "Default")
      (node (ref "U2") (pin "B13") (pinfunction "PT28C_B13") (pintype "bidirectional"))
    )
    (net (code "87") (name "unconnected-(U3-AN45{slash}C1INA{slash}RPB5{slash}RB5-Pad11)") (class "Default")
      (node (ref "U3") (pin "11") (pinfunction "AN45/C1INA/RPB5/RB5_11") (pintype "bidirectional"))
    )
    (net (code "88") (name "unconnected-(U3-AN49{slash}RPB9{slash}PMA7{slash}RB9-Pad22)") (class "Default")
      (node (ref "U3") (pin "22") (pinfunction "AN49/RPB9/PMA7/RB9_22") (pintype "bidirectional"))
    )
    (net (code "89") (name "unconnected-(U3-PGEC2{slash}AN46{slash}RPB6{slash}RB6-Pad17)") (class "Default")
      (node (ref "U3") (pin "17") (pinfunction "PGEC2/AN46/RPB6/RB6_17") (pintype "bidirectional"))
    )
    (net (code "90") (name "unconnected-(U3-TDI{slash}AN8{slash}RB13-Pad28)") (class "Default")
      (node (ref "U3") (pin "28") (pinfunction "TDI/AN8/RB13_28") (pintype "bidirectional"))
    )
    (net (code "91") (name "unconnected-(U3-TMS{slash}CVREFOUT{slash}AN5{slash}RPB10{slash}PMA13{slash}RB10-Pad23)") (class "Default")
      (node (ref "U3") (pin "23") (pinfunction "TMS/CVREFOUT/AN5/RPB10/PMA13/RB10_23") (pintype "bidirectional"))
    )
  )
)
